# Quad_FC_power_V10_2.net
KiCad netlist of a schematic drawn in Altium Designer
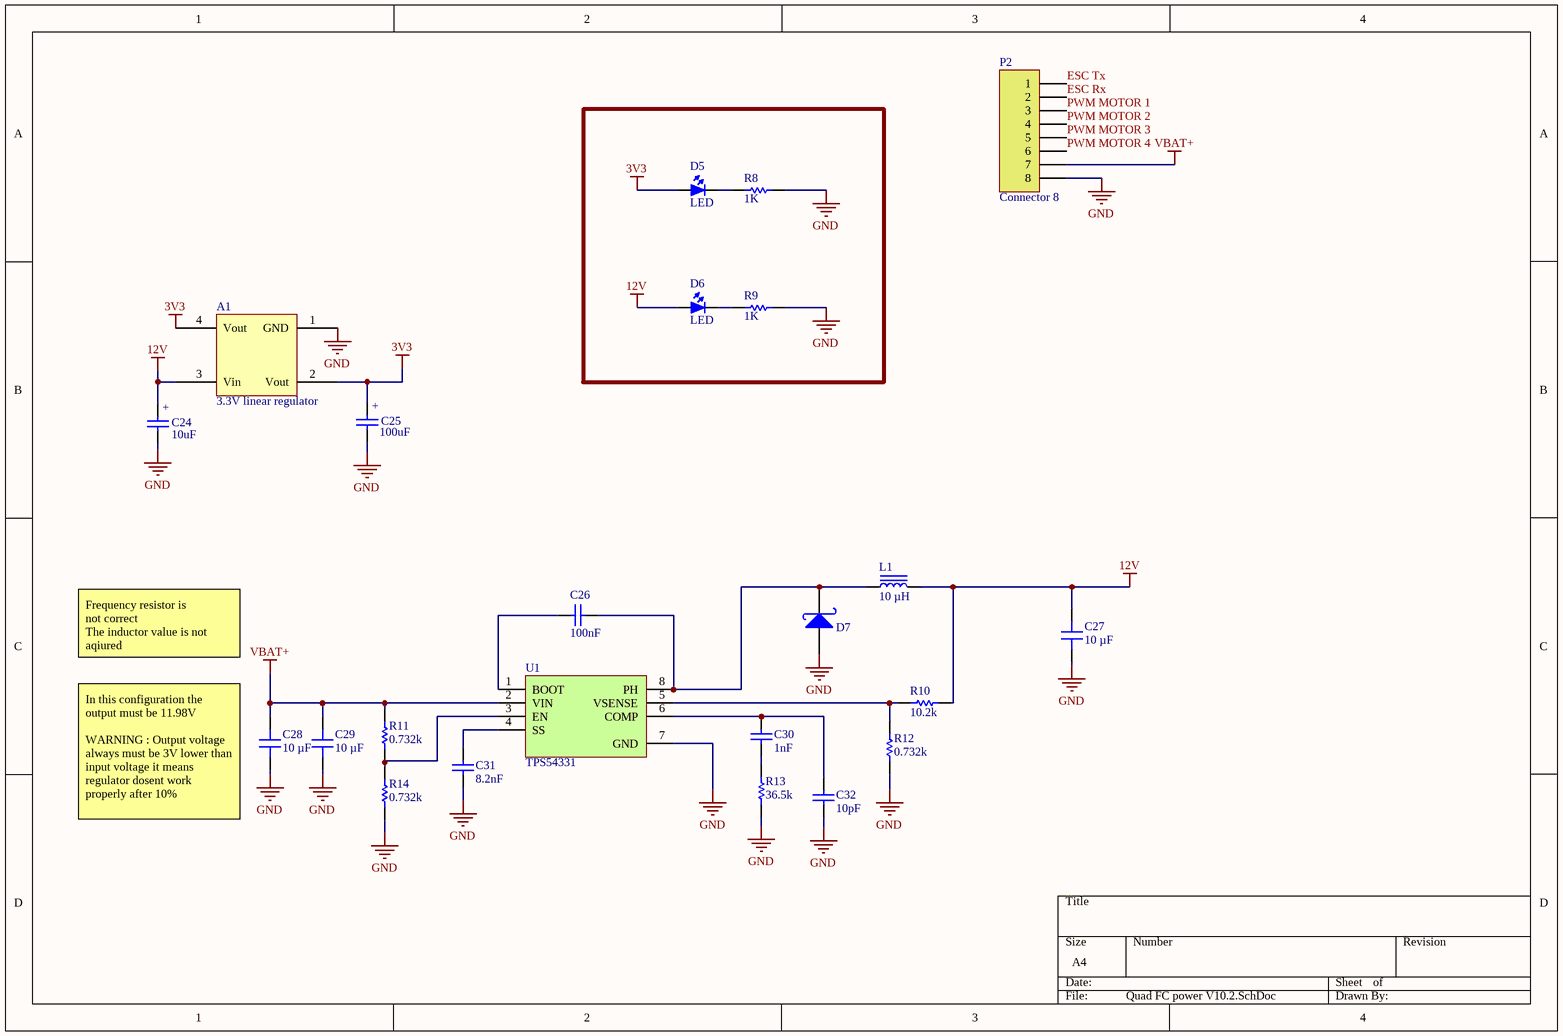
[diagram p0: Quad FC power V10.2.SchDoc]

(export (version "E")
  (design (tool "Eeschema 10.0.6"))
  (components
    (comp (ref "A1")
      (value "3.3V linear regulator")
      (footprint "SOT230P700X180-4N")
      (libsource (lib "Integrated_Library1") (part "ams1117"))
    )
    (comp (ref "C24")
      (value "10uF")
      (footprint "MY_CAP_SMD-B")
      (description "3.5X2.8MM")
      (libsource (lib "AMINLIB") (part "CAP_TANTAL_B"))
    )
    (comp (ref "C25")
      (value "100uF")
      (footprint "MY_CAP_SMD-B")
      (description "3.5X2.8MM")
      (libsource (lib "AMINLIB") (part "CAP_TANTAL_B"))
    )
    (comp (ref "C26")
      (value "100nF")
      (footprint "CAP0603")
      (description "F407VET6 Power CAP")
      (fields (field (name "DESIGNER") "Abbas Basereh"))
      (libsource (lib "2017AbbasBasereh9365731239 -ver1") (part "CAP SMD PACKAGE"))
    )
    (comp (ref "C27")
      (value "10 µF")
      (footprint "CAP 0805_2012")
      (description "CAP CER 10UF 50V X5R 0805")
      (fields
        (field (name "PART NUMBER") "GRM21BR61H106KE43K")
        (field (name "MANUFACTURER") "Murata Electronics")
      )
      (libsource (lib "Celestial Altium Library - altium_library (1)") (part "Capacitor"))
    )
    (comp (ref "C28")
      (value "10 µF")
      (footprint "CAP 0805_2012")
      (description "CAP CER 10UF 50V X5R 0805")
      (fields
        (field (name "PART NUMBER") "GRM21BR61H106KE43K")
        (field (name "MANUFACTURER") "Murata Electronics")
      )
      (libsource (lib "Celestial Altium Library - altium_library (1)") (part "Capacitor"))
    )
    (comp (ref "C29")
      (value "10 µF")
      (footprint "CAP 0805_2012")
      (description "CAP CER 10UF 50V X5R 0805")
      (fields
        (field (name "PART NUMBER") "GRM21BR61H106KE43K")
        (field (name "MANUFACTURER") "Murata Electronics")
      )
      (libsource (lib "Celestial Altium Library - altium_library (1)") (part "Capacitor"))
    )
    (comp (ref "C30")
      (value "1nF")
      (footprint "CAP0603")
      (description "F407VET6 Power CAP")
      (fields (field (name "DESIGNER") "Abbas Basereh"))
      (libsource (lib "2017AbbasBasereh9365731239 -ver1") (part "CAP SMD PACKAGE"))
    )
    (comp (ref "C31")
      (value "8.2nF")
      (footprint "CAP0603")
      (description "F407VET6 Power CAP")
      (fields (field (name "DESIGNER") "Abbas Basereh"))
      (libsource (lib "2017AbbasBasereh9365731239 -ver1") (part "CAP SMD PACKAGE"))
    )
    (comp (ref "C32")
      (value "10pF")
      (footprint "CAP0603")
      (description "F407VET6 Power CAP")
      (fields (field (name "DESIGNER") "Abbas Basereh"))
      (libsource (lib "2017AbbasBasereh9365731239 -ver1") (part "CAP SMD PACKAGE"))
    )
    (comp (ref "D5")
      (value "LED")
      (footprint "0603 - LED")
      (description "Led")
      (fields (field (name "PUBLISHER") "Altium Limited"))
      (libsource (lib "Sajad_Altium_Library") (part "LED"))
    )
    (comp (ref "D6")
      (value "LED")
      (footprint "0603 - LED")
      (description "Led")
      (fields (field (name "PUBLISHER") "Altium Limited"))
      (libsource (lib "Sajad_Altium_Library") (part "LED"))
    )
    (comp (ref "D7")
      (value "1n5822")
      (footprint "SS34:DIOM4226X244N")
      (description "Schottky Rectifiers")
      (fields
        (field (name "MANUFACTURER") "ON Semiconductor/Fairchild")
        (field (name "DESIGNER") "Abbas Basereh")
      )
      (libsource (lib "2017AbbasBasereh9365731239 -ver1") (part "1n5822 SMD"))
    )
    (comp (ref "L1")
      (value "10 µH")
      (footprint "TAIYO YUDEN NRS8030")
      (description "FIXED IND 10UH 3A 42.9 MOHM SMD")
      (fields (field (name "PART NUMBER") "NRS8030T100MJGJV") (field (name "MANUFACTURER") "Taiyo Yuden"))
      (libsource (lib "Celestial Altium Library - altium_library (1)") (part "Inductor"))
    )
    (comp (ref "P2")
      (value "Connector 8")
      (footprint "JST B8B-PH-K")
      (description "Connector, 8-Pin2.5mm")
      (fields (field (name "PUBLISHER") "Altium Limited"))
      (libsource (lib "Sajad_Altium_Library") (part "Connector1x8"))
    )
    (comp (ref "R8")
      (value "1K")
      (footprint "RES0603")
      (description "TOTAL SMD RESISTOR PACK")
      (fields (field (name "DESIGNER") "Abbas Basereh"))
      (libsource (lib "2017AbbasBasereh9365731239 -ver1") (part "RES SMD PACKAGE"))
    )
    (comp (ref "R9")
      (value "1K")
      (footprint "RES0603")
      (description "TOTAL SMD RESISTOR PACK")
      (fields (field (name "DESIGNER") "Abbas Basereh"))
      (libsource (lib "2017AbbasBasereh9365731239 -ver1") (part "RES SMD PACKAGE"))
    )
    (comp (ref "R10")
      (value "10.2k")
      (footprint "RES0603")
      (description "TOTAL SMD RESISTOR PACK")
      (fields (field (name "DESIGNER") "Abbas Basereh"))
      (libsource (lib "2017AbbasBasereh9365731239 -ver1") (part "RES SMD PACKAGE"))
    )
    (comp (ref "R11")
      (value "0.732k")
      (footprint "RES0603")
      (description "TOTAL SMD RESISTOR PACK")
      (fields (field (name "DESIGNER") "Abbas Basereh"))
      (libsource (lib "2017AbbasBasereh9365731239 -ver1") (part "RES SMD PACKAGE"))
    )
    (comp (ref "R12")
      (value "0.732k")
      (footprint "RES0603")
      (description "TOTAL SMD RESISTOR PACK")
      (fields (field (name "DESIGNER") "Abbas Basereh"))
      (libsource (lib "2017AbbasBasereh9365731239 -ver1") (part "RES SMD PACKAGE"))
    )
    (comp (ref "R13")
      (value "36.5k")
      (footprint "RES0603")
      (description "TOTAL SMD RESISTOR PACK")
      (fields (field (name "Comment") "36.5K") (field (name "DESIGNER") "Abbas Basereh"))
      (libsource (lib "2017AbbasBasereh9365731239 -ver1") (part "RES SMD PACKAGE"))
    )
    (comp (ref "R14")
      (value "0.732k")
      (footprint "RES0603")
      (description "TOTAL SMD RESISTOR PACK")
      (fields (field (name "DESIGNER") "Abbas Basereh"))
      (libsource (lib "2017AbbasBasereh9365731239 -ver1") (part "RES SMD PACKAGE"))
    )
    (comp (ref "U1")
      (value "TPS54331")
      (footprint "SO8")
      (description "DC/DC Switching Regulators 2A,28V,1MHz Step Down SWIFT DC/D;Output Voltage:0.8 V to 25 V")
      (libsource (lib "Sajad_Altium_Library") (part "TPS54331"))
    )
  )
  (nets
    (net (code "1") (name "/ESC Rx") (class "Default")
      (node (ref "P2") (pin "2") (pinfunction "2_2") (pintype "passive"))
    )
    (net (code "2") (name "/ESC Tx") (class "Default")
      (node (ref "P2") (pin "1") (pinfunction "1_1") (pintype "passive"))
    )
    (net (code "3") (name "/PWM MOTOR 1") (class "Default")
      (node (ref "P2") (pin "3") (pinfunction "3_3") (pintype "passive"))
    )
    (net (code "4") (name "/PWM MOTOR 2") (class "Default")
      (node (ref "P2") (pin "4") (pinfunction "4_4") (pintype "passive"))
    )
    (net (code "5") (name "/PWM MOTOR 3") (class "Default")
      (node (ref "P2") (pin "5") (pinfunction "5_5") (pintype "passive"))
    )
    (net (code "6") (name "/PWM MOTOR 4") (class "Default")
      (node (ref "P2") (pin "6") (pinfunction "6_6") (pintype "passive"))
    )
    (net (code "7") (name "3V3") (class "Default")
      (node (ref "A1") (pin "2") (pinfunction "Vout_2") (pintype "passive"))
      (node (ref "A1") (pin "4") (pinfunction "Vout_4") (pintype "passive"))
      (node (ref "C25") (pin "+") (pinfunction "+_+") (pintype "passive"))
      (node (ref "D5") (pin "1") (pinfunction "A_1") (pintype "passive"))
    )
    (net (code "8") (name "12V") (class "Default")
      (node (ref "A1") (pin "3") (pinfunction "Vin_3") (pintype "passive"))
      (node (ref "C24") (pin "+") (pinfunction "+_+") (pintype "passive"))
      (node (ref "C27") (pin "2") (pinfunction "2_2") (pintype "passive"))
      (node (ref "D6") (pin "1") (pinfunction "A_1") (pintype "passive"))
      (node (ref "L1") (pin "2") (pinfunction "2_2") (pintype "passive"))
      (node (ref "R10") (pin "2") (pinfunction "2_2") (pintype "passive"))
    )
    (net (code "9") (name "GND") (class "Default")
      (node (ref "A1") (pin "1") (pinfunction "GND_1") (pintype "passive"))
      (node (ref "C24") (pin "-") (pinfunction "-_-") (pintype "passive"))
      (node (ref "C25") (pin "-") (pinfunction "-_-") (pintype "passive"))
      (node (ref "C27") (pin "1") (pinfunction "1_1") (pintype "passive"))
      (node (ref "C28") (pin "1") (pinfunction "1_1") (pintype "passive"))
      (node (ref "C29") (pin "1") (pinfunction "1_1") (pintype "passive"))
      (node (ref "C31") (pin "2") (pinfunction "2_2") (pintype "passive"))
      (node (ref "C32") (pin "2") (pinfunction "2_2") (pintype "passive"))
      (node (ref "D7") (pin "1") (pinfunction "A_1") (pintype "passive"))
      (node (ref "P2") (pin "8") (pinfunction "8_8") (pintype "passive"))
      (node (ref "R12") (pin "1") (pinfunction "1_1") (pintype "passive"))
      (node (ref "R13") (pin "1") (pinfunction "1_1") (pintype "passive"))
      (node (ref "R14") (pin "1") (pinfunction "1_1") (pintype "passive"))
      (node (ref "R8") (pin "2") (pinfunction "2_2") (pintype "passive"))
      (node (ref "R9") (pin "2") (pinfunction "2_2") (pintype "passive"))
      (node (ref "U1") (pin "7") (pinfunction "GND_7") (pintype "passive"))
    )
    (net (code "10") (name "Net-(C30-Pad2)") (class "Default")
      (node (ref "C30") (pin "2") (pinfunction "2_2") (pintype "passive"))
      (node (ref "R13") (pin "2") (pinfunction "2_2") (pintype "passive"))
    )
    (net (code "11") (name "Net-(D5-K)") (class "Default")
      (node (ref "D5") (pin "2") (pinfunction "K_2") (pintype "passive"))
      (node (ref "R8") (pin "1") (pinfunction "1_1") (pintype "passive"))
    )
    (net (code "12") (name "Net-(D6-K)") (class "Default")
      (node (ref "D6") (pin "2") (pinfunction "K_2") (pintype "passive"))
      (node (ref "R9") (pin "1") (pinfunction "1_1") (pintype "passive"))
    )
    (net (code "13") (name "Net-(D7-K)") (class "Default")
      (node (ref "C26") (pin "1") (pinfunction "1_1") (pintype "passive"))
      (node (ref "D7") (pin "2") (pinfunction "K_2") (pintype "passive"))
      (node (ref "L1") (pin "1") (pinfunction "1_1") (pintype "passive"))
      (node (ref "U1") (pin "8") (pinfunction "PH_8") (pintype "open_collector"))
    )
    (net (code "14") (name "Net-(U1-BOOT)") (class "Default")
      (node (ref "C26") (pin "2") (pinfunction "2_2") (pintype "passive"))
      (node (ref "U1") (pin "1") (pinfunction "BOOT_1") (pintype "passive"))
    )
    (net (code "15") (name "Net-(U1-COMP)") (class "Default")
      (node (ref "C30") (pin "1") (pinfunction "1_1") (pintype "passive"))
      (node (ref "C32") (pin "1") (pinfunction "1_1") (pintype "passive"))
      (node (ref "U1") (pin "6") (pinfunction "COMP_6") (pintype "power_in"))
    )
    (net (code "16") (name "Net-(U1-EN)") (class "Default")
      (node (ref "R11") (pin "1") (pinfunction "1_1") (pintype "passive"))
      (node (ref "R14") (pin "2") (pinfunction "2_2") (pintype "passive"))
      (node (ref "U1") (pin "3") (pinfunction "EN_3") (pintype "passive"))
    )
    (net (code "17") (name "Net-(U1-SS)") (class "Default")
      (node (ref "C31") (pin "1") (pinfunction "1_1") (pintype "passive"))
      (node (ref "U1") (pin "4") (pinfunction "SS_4") (pintype "power_in"))
    )
    (net (code "18") (name "Net-(U1-VSENSE)") (class "Default")
      (node (ref "R10") (pin "1") (pinfunction "1_1") (pintype "passive"))
      (node (ref "R12") (pin "2") (pinfunction "2_2") (pintype "passive"))
      (node (ref "U1") (pin "5") (pinfunction "VSENSE_5") (pintype "passive"))
    )
    (net (code "19") (name "VBAT+") (class "Default")
      (node (ref "C28") (pin "2") (pinfunction "2_2") (pintype "passive"))
      (node (ref "C29") (pin "2") (pinfunction "2_2") (pintype "passive"))
      (node (ref "P2") (pin "7") (pinfunction "7_7") (pintype "passive"))
      (node (ref "R11") (pin "2") (pinfunction "2_2") (pintype "passive"))
      (node (ref "U1") (pin "2") (pinfunction "VIN_2") (pintype "passive"))
    )
  )
)
